# STM32_microcontroller_RF.net
KiCad netlist of a schematic drawn in Altium Designer
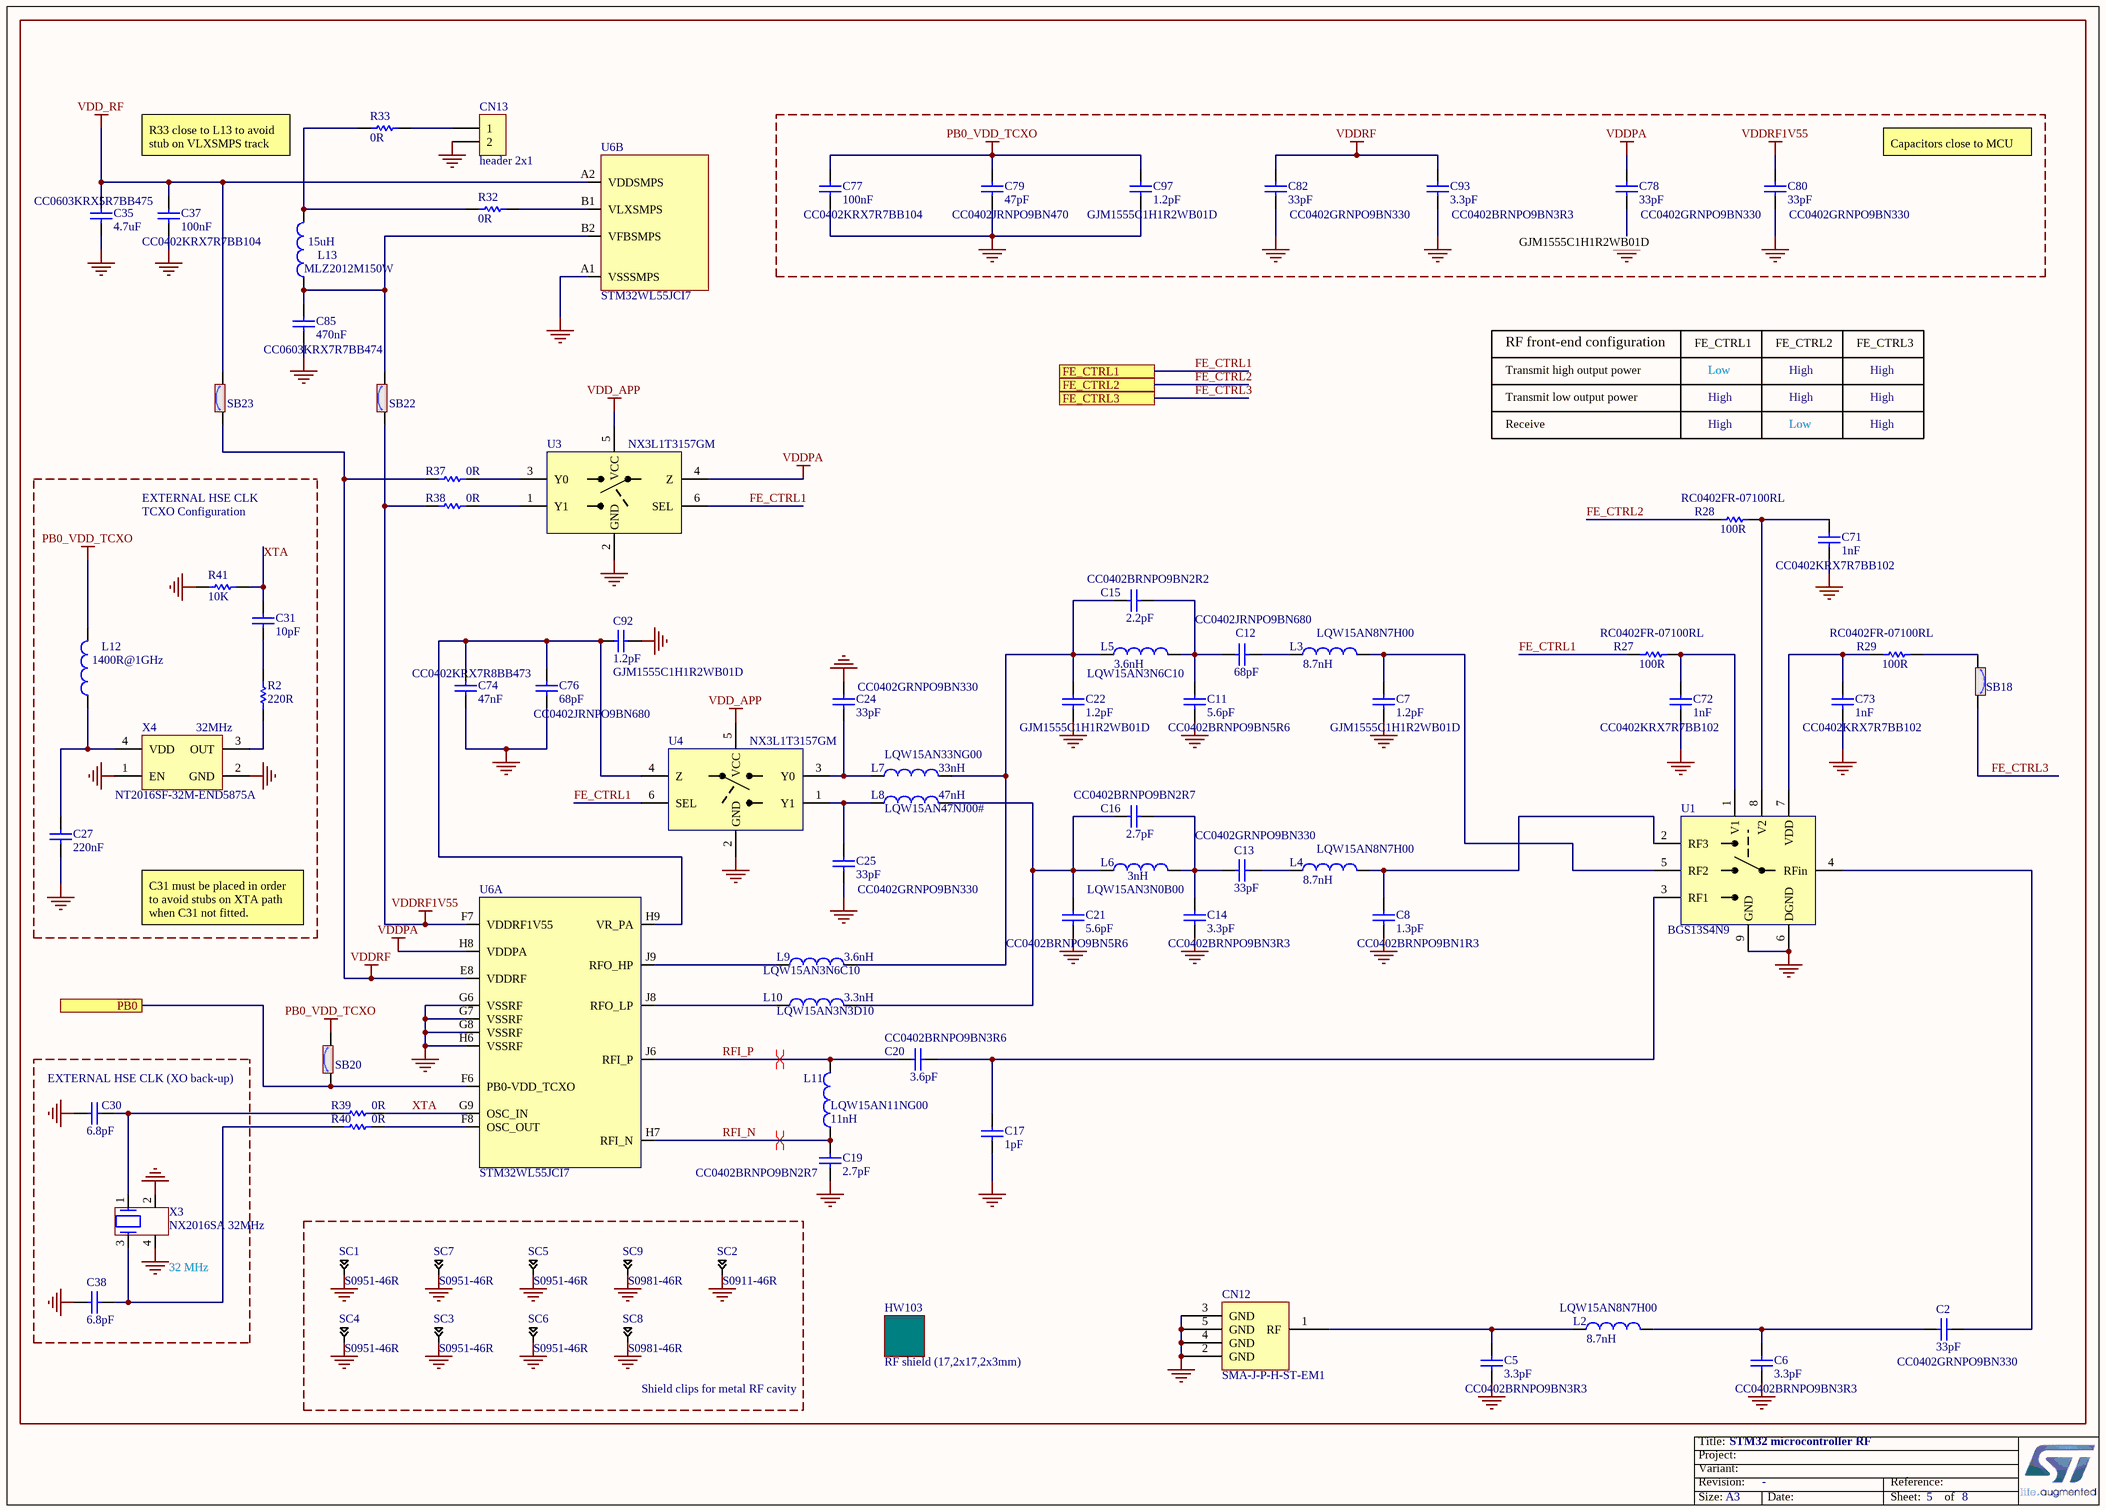
[diagram p0: STM32_microcontroller_RF.SchDoc]

(export (version "E")
  (design (tool "Eeschema 10.0.6"))
  (components
    (comp (ref "C2")
      (value "33pF")
      (footprint "C0402")
      (description "Capacitor, MLCC, 33pF, 50V, NPO, +/-2%, 0402, T=0,5mm")
      (fields
        (field (name "INTERNAL_PART_NUMBER") "MCD-01784")
        (field (name "MANUFACTURER_PART_NUMBER") "CC0402GRNPO9BN330")
        (field (name "MANUFACTURER") "YAGEO")
        (field (name "PROVIDED_BY") "SUBCO")
      )
      (libsource (lib "MCD_PARTS_database") (part "Capacitor"))
    )
    (comp (ref "C5")
      (value "3.3pF")
      (footprint "C0402")
      (description "Capacitor, MLCC, 3.3pF, 50V, NPO, +/-0.1pF, 0402, T=0,5mm")
      (fields
        (field (name "INTERNAL_PART_NUMBER") "MCD-01775")
        (field (name "MANUFACTURER_PART_NUMBER") "CC0402BRNPO9BN3R3")
        (field (name "MANUFACTURER") "YAGEO")
        (field (name "PROVIDED_BY") "SUBCO")
      )
      (libsource (lib "MCD_PARTS_database") (part "Capacitor"))
    )
    (comp (ref "C6")
      (value "3.3pF")
      (footprint "C0402")
      (description "Capacitor, MLCC, 3.3pF, 50V, NPO, +/-0.1pF, 0402, T=0,5mm")
      (fields
        (field (name "INTERNAL_PART_NUMBER") "MCD-01775")
        (field (name "MANUFACTURER_PART_NUMBER") "CC0402BRNPO9BN3R3")
        (field (name "MANUFACTURER") "YAGEO")
        (field (name "PROVIDED_BY") "SUBCO")
      )
      (libsource (lib "MCD_PARTS_database") (part "Capacitor"))
    )
    (comp (ref "C7")
      (value "1.2pF")
      (footprint "C0402")
      (description "Capacitor, High Q type for high frequency and high power, SMD, 1.2pF, 50V, 0,05pf, 0402")
      (fields
        (field (name "INTERNAL_PART_NUMBER") "MCD-02065")
        (field (name "MANUFACTURER") "MURATA")
        (field (name "MANUFACTURER_PART_NUMBER") "GJM1555C1H1R2WB01D")
      )
      (libsource (lib "MCD_PARTS_database") (part "Capacitor"))
    )
    (comp (ref "C8")
      (value "1.3pF")
      (footprint "C0402")
      (description "Capacitor, MLCC, 1.3pF, 50V, NPO, +/-0.1pF, 0402, T=0,5mm")
      (fields
        (field (name "INTERNAL_PART_NUMBER") "MCD-01772")
        (field (name "MANUFACTURER_PART_NUMBER") "CC0402BRNPO9BN1R3")
        (field (name "MANUFACTURER") "YAGEO")
        (field (name "PROVIDED_BY") "SUBCO")
      )
      (libsource (lib "MCD_PARTS_database") (part "Capacitor"))
    )
    (comp (ref "C11")
      (value "5.6pF")
      (footprint "C0402")
      (description "Capacitor, MLCC, 5.6pF, 50V, NPO, +/- 0.1pF, 0402, T=0,5mm")
      (fields
        (field (name "INTERNAL_PART_NUMBER") "MCD-01374")
        (field (name "MANUFACTURER") "YAGEO")
        (field (name "MANUFACTURER_PART_NUMBER") "CC0402BRNPO9BN5R6")
      )
      (libsource (lib "MCD_PARTS_database") (part "Capacitor"))
    )
    (comp (ref "C12")
      (value "68pF")
      (footprint "C0402")
      (description "Capacitor, MLCC, 68pF, 50V, NPO, +/-5%, 0402, T=0,5mm")
      (fields
        (field (name "INTERNAL_PART_NUMBER") "MCD-01604")
        (field (name "MANUFACTURER") "YAGEO")
        (field (name "MANUFACTURER_PART_NUMBER") "CC0402JRNPO9BN680")
      )
      (libsource (lib "MCD_PARTS_database") (part "Capacitor"))
    )
    (comp (ref "C13")
      (value "33pF")
      (footprint "C0402")
      (description "Capacitor, MLCC, 33pF, 50V, NPO, +/-2%, 0402, T=0,5mm")
      (fields
        (field (name "INTERNAL_PART_NUMBER") "MCD-01784")
        (field (name "MANUFACTURER_PART_NUMBER") "CC0402GRNPO9BN330")
        (field (name "MANUFACTURER") "YAGEO")
        (field (name "PROVIDED_BY") "SUBCO")
      )
      (libsource (lib "MCD_PARTS_database") (part "Capacitor"))
    )
    (comp (ref "C14")
      (value "3.3pF")
      (footprint "C0402")
      (description "Capacitor, MLCC, 3.3pF, 50V, NPO, +/-0.1pF, 0402, T=0,5mm")
      (fields
        (field (name "INTERNAL_PART_NUMBER") "MCD-01775")
        (field (name "MANUFACTURER_PART_NUMBER") "CC0402BRNPO9BN3R3")
        (field (name "MANUFACTURER") "YAGEO")
        (field (name "PROVIDED_BY") "SUBCO")
      )
      (libsource (lib "MCD_PARTS_database") (part "Capacitor"))
    )
    (comp (ref "C15")
      (value "2.2pF")
      (footprint "C0402")
      (description "Capacitor, MLCC, 2.2pF, 50V, NPO, +/-0.1pF, 0402, T=0,5mm")
      (fields
        (field (name "INTERNAL_PART_NUMBER") "MCD-01773")
        (field (name "MANUFACTURER") "YAGEO")
        (field (name "MANUFACTURER_PART_NUMBER") "CC0402BRNPO9BN2R2")
      )
      (libsource (lib "MCD_PARTS_database") (part "Capacitor"))
    )
    (comp (ref "C16")
      (value "2.7pF")
      (footprint "C0402")
      (description "Capacitor, MLCC, 2.7pF, 50V, NPO, +/-0.1pF, 0402, T=0,5mm")
      (fields
        (field (name "INTERNAL_PART_NUMBER") "MCD-01774")
        (field (name "MANUFACTURER_PART_NUMBER") "CC0402BRNPO9BN2R7")
        (field (name "MANUFACTURER") "YAGEO")
        (field (name "PROVIDED_BY") "SUBCO")
      )
      (libsource (lib "MCD_PARTS_database") (part "Capacitor"))
    )
    (comp (ref "C17")
      (value "1pF")
      (footprint "C0402")
      (description "Capacitor, MLCC, 1pF, 50V, NPO, +/-0.1pF, 0402, T=0,5mm")
      (fields (field (name "INTERNAL_PART_NUMBER") "MCD-01600") (field (name "MANUFACTURER") "YAGEO"))
      (libsource (lib "MCD_PARTS_database") (part "Capacitor"))
    )
    (comp (ref "C19")
      (value "2.7pF")
      (footprint "C0402")
      (description "Capacitor, MLCC, 2.7pF, 50V, NPO, +/-0.1pF, 0402, T=0,5mm")
      (fields
        (field (name "INTERNAL_PART_NUMBER") "MCD-01774")
        (field (name "MANUFACTURER_PART_NUMBER") "CC0402BRNPO9BN2R7")
        (field (name "MANUFACTURER") "YAGEO")
        (field (name "PROVIDED_BY") "SUBCO")
      )
      (libsource (lib "MCD_PARTS_database") (part "Capacitor"))
    )
    (comp (ref "C20")
      (value "3.6pF")
      (footprint "C0402")
      (description "Capacitor, MLCC, 3.6pF, 50V, NPO, +/-0.1pF, 0402, T=0,5mm")
      (fields
        (field (name "INTERNAL_PART_NUMBER") "MCD-01776")
        (field (name "MANUFACTURER_PART_NUMBER") "CC0402BRNPO9BN3R6")
        (field (name "MANUFACTURER") "YAGEO")
        (field (name "PROVIDED_BY") "SUBCO")
      )
      (libsource (lib "MCD_PARTS_database") (part "Capacitor"))
    )
    (comp (ref "C21")
      (value "5.6pF")
      (footprint "C0402")
      (description "Capacitor, MLCC, 5.6pF, 50V, NPO, +/- 0.1pF, 0402, T=0,5mm")
      (fields
        (field (name "INTERNAL_PART_NUMBER") "MCD-01374")
        (field (name "MANUFACTURER_PART_NUMBER") "CC0402BRNPO9BN5R6")
        (field (name "MANUFACTURER") "YAGEO")
        (field (name "PROVIDED_BY") "SUBCO")
      )
      (libsource (lib "MCD_PARTS_database") (part "Capacitor"))
    )
    (comp (ref "C22")
      (value "1.2pF")
      (footprint "C0402")
      (description "Capacitor, High Q type for high frequency and high power, SMD, 1.2pF, 50V, 0,05pf, 0402")
      (fields
        (field (name "INTERNAL_PART_NUMBER") "MCD-02065")
        (field (name "MANUFACTURER") "MURATA")
        (field (name "MANUFACTURER_PART_NUMBER") "GJM1555C1H1R2WB01D")
      )
      (libsource (lib "MCD_PARTS_database") (part "Capacitor"))
    )
    (comp (ref "C24")
      (value "33pF")
      (footprint "C0402")
      (description "Capacitor, MLCC, 33pF, 50V, NPO, +/-2%, 0402, T=0,5mm")
      (fields
        (field (name "INTERNAL_PART_NUMBER") "MCD-01784")
        (field (name "MANUFACTURER_PART_NUMBER") "CC0402GRNPO9BN330")
        (field (name "MANUFACTURER") "YAGEO")
        (field (name "PROVIDED_BY") "SUBCO")
      )
      (libsource (lib "MCD_PARTS_database") (part "Capacitor"))
    )
    (comp (ref "C25")
      (value "33pF")
      (footprint "C0402")
      (description "Capacitor, MLCC, 33pF, 50V, NPO, +/-2%, 0402, T=0,5mm")
      (fields
        (field (name "INTERNAL_PART_NUMBER") "MCD-01784")
        (field (name "MANUFACTURER_PART_NUMBER") "CC0402GRNPO9BN330")
        (field (name "MANUFACTURER") "YAGEO")
        (field (name "PROVIDED_BY") "SUBCO")
      )
      (libsource (lib "MCD_PARTS_database") (part "Capacitor"))
    )
    (comp (ref "C27")
      (value "220nF")
      (footprint "C0402")
      (description "Capacitor, MLCC, 220nF, 16V, X7R, +/-10%, ,0402, T=0,5mm")
      (fields (field (name "INTERNAL_PART_NUMBER") "MCD-00602") (field (name "MANUFACTURER") "TDK"))
      (libsource (lib "MCD_PARTS_database") (part "Capacitor"))
    )
    (comp (ref "C30")
      (value "6.8pF")
      (footprint "C0402")
      (description "Capacitor, MLCC, 6.8pF, 50V, NPO, +-0.25pF, 0402, T=0.5mm")
      (fields
        (field (name "INTERNAL_PART_NUMBER") "MCD-00674")
        (field (name "MANUFACTURER_PART_NUMBER") "CC0402CRNPO9BN6R8")
        (field (name "PROVIDED_BY") "SUBCO")
      )
      (libsource (lib "MCD_PARTS_database") (part "Capacitor"))
    )
    (comp (ref "C31")
      (value "10pF")
      (footprint "C0402")
      (description "Capacitor, MLCC, 10pF, 50V, NPO, +/-5%, 0402, T=0,5mm")
      (fields (field (name "INTERNAL_PART_NUMBER") "MCD-00015") (field (name "MANUFACTURER") "YAGEO"))
      (libsource (lib "MCD_PARTS_database") (part "Capacitor"))
    )
    (comp (ref "C35")
      (value "4.7uF")
      (footprint "C0603")
      (description "Capacitor, MLCC, 4.7uF, 16V, X5R, 10%, 0603, T=0.8mm")
      (fields
        (field (name "INTERNAL_PART_NUMBER") "MCD-00009")
        (field (name "MANUFACTURER_PART_NUMBER") "CC0603KRX5R7BB475")
        (field (name "MANUFACTURER") "YAGEO")
        (field (name "PROVIDED_BY") "SUBCO")
      )
      (libsource (lib "MCD_PARTS_database") (part "Capacitor"))
    )
    (comp (ref "C37")
      (value "100nF")
      (footprint "C0402")
      (description "Capacitor, MLCC, 100nF, 16V, X7R, 10%, 0402, T=0,5mm")
      (fields
        (field (name "INTERNAL_PART_NUMBER") "MCD-00102")
        (field (name "MANUFACTURER_PART_NUMBER") "CC0402KRX7R7BB104")
        (field (name "MANUFACTURER") "YAGEO")
        (field (name "PROVIDED_BY") "SUBCO")
      )
      (libsource (lib "MCD_PARTS_database") (part "Capacitor"))
    )
    (comp (ref "C38")
      (value "6.8pF")
      (footprint "C0402")
      (description "Capacitor, MLCC, 6.8pF, 50V, NPO, +-0.25pF, 0402, T=0.5mm")
      (fields
        (field (name "INTERNAL_PART_NUMBER") "MCD-00674")
        (field (name "MANUFACTURER_PART_NUMBER") "CC0402CRNPO9BN6R8")
        (field (name "PROVIDED_BY") "SUBCO")
      )
      (libsource (lib "MCD_PARTS_database") (part "Capacitor"))
    )
    (comp (ref "C71")
      (value "1nF")
      (footprint "C0402")
      (description "Capacitor, MLCC, 1nF, 16V, X7R, 10%, 0402, T=0.5mm")
      (fields
        (field (name "INTERNAL_PART_NUMBER") "MCD-00198")
        (field (name "MANUFACTURER_PART_NUMBER") "CC0402KRX7R7BB102")
        (field (name "MANUFACTURER") "YAGEO")
        (field (name "PROVIDED_BY") "SUBCO")
      )
      (libsource (lib "MCD_PARTS_database") (part "Capacitor"))
    )
    (comp (ref "C72")
      (value "1nF")
      (footprint "C0402")
      (description "Capacitor, MLCC, 1nF, 16V, X7R, 10%, 0402, T=0.5mm")
      (fields
        (field (name "INTERNAL_PART_NUMBER") "MCD-00198")
        (field (name "MANUFACTURER_PART_NUMBER") "CC0402KRX7R7BB102")
        (field (name "MANUFACTURER") "YAGEO")
        (field (name "PROVIDED_BY") "SUBCO")
      )
      (libsource (lib "MCD_PARTS_database") (part "Capacitor"))
    )
    (comp (ref "C73")
      (value "1nF")
      (footprint "C0402")
      (description "Capacitor, MLCC, 1nF, 16V, X7R, 10%, 0402, T=0.5mm")
      (fields
        (field (name "INTERNAL_PART_NUMBER") "MCD-00198")
        (field (name "MANUFACTURER_PART_NUMBER") "CC0402KRX7R7BB102")
        (field (name "MANUFACTURER") "YAGEO")
        (field (name "PROVIDED_BY") "SUBCO")
      )
      (libsource (lib "MCD_PARTS_database") (part "Capacitor"))
    )
    (comp (ref "C74")
      (value "47nF")
      (footprint "C0402")
      (description "Capacitor, MLCC, 47nF, 25V, X7R, +-10%, 0402, T=0,5mm")
      (fields
        (field (name "INTERNAL_PART_NUMBER") "MCD-01605")
        (field (name "MANUFACTURER_PART_NUMBER") "CC0402KRX7R8BB473")
        (field (name "MANUFACTURER") "YAGEO")
        (field (name "PROVIDED_BY") "SUBCO")
      )
      (libsource (lib "MCD_PARTS_database") (part "Capacitor"))
    )
    (comp (ref "C76")
      (value "68pF")
      (footprint "C0402")
      (description "Capacitor, MLCC, 68pF, 50V, NPO, +-5%, 0402, T=0,5mm")
      (fields
        (field (name "INTERNAL_PART_NUMBER") "MCD-01604")
        (field (name "MANUFACTURER_PART_NUMBER") "CC0402JRNPO9BN680")
        (field (name "MANUFACTURER") "YAGEO")
        (field (name "PROVIDED_BY") "SUBCO")
      )
      (libsource (lib "MCD_PARTS_database") (part "Capacitor"))
    )
    (comp (ref "C77")
      (value "100nF")
      (footprint "C0402")
      (description "Capacitor, MLCC, 100nF, 16V, X7R, 10%, 0402, T=0,5mm")
      (fields
        (field (name "INTERNAL_PART_NUMBER") "MCD-00102")
        (field (name "MANUFACTURER_PART_NUMBER") "CC0402KRX7R7BB104")
        (field (name "MANUFACTURER") "YAGEO")
        (field (name "PROVIDED_BY") "SUBCO")
      )
      (libsource (lib "MCD_PARTS_database") (part "Capacitor"))
    )
    (comp (ref "C78")
      (value "33pF")
      (footprint "C0402")
      (description "Capacitor, MLCC, 33pF, 50V, NPO, +/-2%, 0402, T=0,5mm")
      (fields
        (field (name "INTERNAL_PART_NUMBER") "MCD-01784")
        (field (name "MANUFACTURER_PART_NUMBER") "CC0402GRNPO9BN330")
        (field (name "MANUFACTURER") "YAGEO")
        (field (name "PROVIDED_BY") "SUBCO")
      )
      (libsource (lib "MCD_PARTS_database") (part "Capacitor"))
    )
    (comp (ref "C79")
      (value "47pF")
      (footprint "C0402")
      (description "Capacitor, MLCC, 147pF, 50V, NPO, +-5%, 0402, T=0,5mm")
      (fields
        (field (name "INTERNAL_PART_NUMBER") "MCD-01603")
        (field (name "MANUFACTURER_PART_NUMBER") "CC0402JRNPO9BN470")
        (field (name "MANUFACTURER") "YAGEO")
        (field (name "PROVIDED_BY") "SUBCO")
      )
      (libsource (lib "MCD_PARTS_database") (part "Capacitor"))
    )
    (comp (ref "C80")
      (value "33pF")
      (footprint "C0402")
      (description "Capacitor, MLCC, 33pF, 50V, NPO, +/-2%, 0402, T=0,5mm")
      (fields
        (field (name "INTERNAL_PART_NUMBER") "MCD-01784")
        (field (name "MANUFACTURER_PART_NUMBER") "CC0402GRNPO9BN330")
        (field (name "MANUFACTURER") "YAGEO")
        (field (name "PROVIDED_BY") "SUBCO")
      )
      (libsource (lib "MCD_PARTS_database") (part "Capacitor"))
    )
    (comp (ref "C82")
      (value "33pF")
      (footprint "C0402")
      (description "Capacitor, MLCC, 33pF, 50V, NPO, +/-2%, 0402, T=0,5mm")
      (fields
        (field (name "INTERNAL_PART_NUMBER") "MCD-01784")
        (field (name "MANUFACTURER_PART_NUMBER") "CC0402GRNPO9BN330")
        (field (name "MANUFACTURER") "YAGEO")
        (field (name "PROVIDED_BY") "SUBCO")
      )
      (libsource (lib "MCD_PARTS_database") (part "Capacitor"))
    )
    (comp (ref "C85")
      (value "470nF")
      (footprint "C0603")
      (description "Capacitor, MLCC, 470nF, 16V, X7R, 10%, 0603, T=0.8mm")
      (fields
        (field (name "INTERNAL_PART_NUMBER") "MCD-01006")
        (field (name "MANUFACTURER_PART_NUMBER") "CC0603KRX7R7BB474")
        (field (name "MANUFACTURER") "YAGEO")
        (field (name "PROVIDED_BY") "SUBCO")
      )
      (libsource (lib "MCD_PARTS_database") (part "Capacitor"))
    )
    (comp (ref "C92")
      (value "1.2pF")
      (footprint "C0402")
      (description "Capacitor, High Q type for high frequency and high power, SMD, 1.2pF, 50V, 0,05pf, 0402")
      (fields
        (field (name "INTERNAL_PART_NUMBER") "MCD-02065")
        (field (name "MANUFACTURER") "MURATA")
        (field (name "MANUFACTURER_PART_NUMBER") "GJM1555C1H1R2WB01D")
      )
      (libsource (lib "MCD_PARTS_database") (part "Capacitor"))
    )
    (comp (ref "C93")
      (value "3.3pF")
      (footprint "C0402")
      (description "Capacitor, MLCC, 3.3pF, 50V, NPO, +/-0.1pF, 0402, T=0,5mm")
      (fields
        (field (name "INTERNAL_PART_NUMBER") "MCD-01775")
        (field (name "MANUFACTURER") "YAGEO")
        (field (name "MANUFACTURER_PART_NUMBER") "CC0402BRNPO9BN3R3")
      )
      (libsource (lib "MCD_PARTS_database") (part "Capacitor"))
    )
    (comp (ref "C97")
      (value "1.2pF")
      (footprint "C0402")
      (description "Capacitor, High Q type for high frequency and high power, SMD, 1.2pF, 50V, 0,05pf, 0402")
      (fields
        (field (name "INTERNAL_PART_NUMBER") "MCD-02065")
        (field (name "MANUFACTURER") "MURATA")
        (field (name "MANUFACTURER_PART_NUMBER") "GJM1555C1H1R2WB01D")
      )
      (libsource (lib "MCD_PARTS_database") (part "Capacitor"))
    )
    (comp (ref "CN12")
      (value "SMA-J-P-H-ST-EM1")
      (footprint "CON_SAMTEC_SMA-J-P-X-ST-EM1")
      (description "RF SMA connector PCB edge")
      (fields
        (field (name "INTERNAL_PART_NUMBER") "MCD-00279")
        (field (name "MANUFACTURER") "SAMTEC")
        (field (name "PROVIDED_BY") "SUBCO")
      )
      (libsource (lib "MCD_PARTS_database") (part "SMA-J-P-H-ST-EM1"))
    )
    (comp (ref "CN13")
      (value "header 2x1")
      (footprint "CON_988-JIUBABA_PHFS25-11-02-G0B115-T-1")
      (description "Header, 2x1, 2.54mm, VR, TH, Height 6mm/3mm")
      (fields
        (field (name "INTERNAL_PART_NUMBER") "MCD-00314")
        (field (name "MANUFACTURER_PART_NUMBER") "PHFS25-11-02-G0B115-T-1")
        (field (name "PROVIDED_BY") "SUBCO")
      )
      (libsource (lib "MCD_PARTS_database") (part "Header 2x1"))
    )
    (comp (ref "HW103")
      (value "RF shield (17,2x17,2x3mm)")
      (footprint "SHIELD_RF_ST-CUSTOM_17P2X17P2_H3")
      (description "RF shield (17,2x17,2x3mm), Brass with Sn finishing, Sheet tickness : 0,2mm")
      (fields (field (name "INTERNAL_PART_NUMBER") "MCD-02088") (field (name "BMS_PART_NUMBER") "TBD"))
      (libsource (lib "MCD_PARTS_database") (part "Daughter_Board"))
    )
    (comp (ref "L2")
      (value "8.7nH")
      (footprint "IND_0402_MURATA_LQW15AN_H0P5")
      (description "0402 inductor, 8.7nH +/-3%, 540mA max, 0.14 ohm DC max, Q min = 25")
      (fields
        (field (name "INTERNAL_PART_NUMBER") "MCD-01768")
        (field (name "MANUFACTURER_PART_NUMBER") "LQW15AN8N7H00")
        (field (name "MANUFACTURER") "MURATA")
        (field (name "PROVIDED_BY") "SUBCO")
      )
      (libsource (lib "MCD_PARTS_database") (part "Inductor"))
    )
    (comp (ref "L3")
      (value "8.7nH")
      (footprint "IND_0402_MURATA_LQW15AN_H0P5")
      (description "0402 inductor, 8.7nH +/-3%, 540mA max, 0.14 ohm DC max, Q min = 25")
      (fields
        (field (name "INTERNAL_PART_NUMBER") "MCD-01768")
        (field (name "MANUFACTURER") "MURATA")
        (field (name "MANUFACTURER_PART_NUMBER") "LQW15AN8N7H00")
      )
      (libsource (lib "MCD_PARTS_database") (part "Inductor"))
    )
    (comp (ref "L4")
      (value "8.7nH")
      (footprint "IND_0402_MURATA_LQW15AN_H0P5")
      (description "0402 inductor, 8.7nH +/-3%, 540mA max, 0.14 ohm DC max, Q min = 25")
      (fields
        (field (name "INTERNAL_PART_NUMBER") "MCD-01768")
        (field (name "MANUFACTURER_PART_NUMBER") "LQW15AN8N7H00")
        (field (name "MANUFACTURER") "MURATA")
        (field (name "PROVIDED_BY") "SUBCO")
      )
      (libsource (lib "MCD_PARTS_database") (part "Inductor"))
    )
    (comp (ref "L5")
      (value "3.6nH")
      (footprint "IND_0402_MURATA_LQW15AN_H0P5")
      (description "0402 inductor, 3.6nH +/-0.2nH, 900mA max, 0.04 ohm DC max, Q min = 30")
      (fields
        (field (name "INTERNAL_PART_NUMBER") "MCD-01762")
        (field (name "MANUFACTURER") "MURATA")
        (field (name "MANUFACTURER_PART_NUMBER") "LQW15AN3N6C10")
      )
      (libsource (lib "MCD_PARTS_database") (part "Inductor"))
    )
    (comp (ref "L6")
      (value "3nH")
      (footprint "IND_0402_MURATA_LQW15AN_H0P5")
      (description "0402 inductor, 3nH +-0.1nH, 750mA max, 0.07 ohm DC max, Q min = 20")
      (fields
        (field (name "INTERNAL_PART_NUMBER") "MCD-01922")
        (field (name "MANUFACTURER_PART_NUMBER") "LQW15AN3N0B00")
        (field (name "MANUFACTURER") "MURATA")
        (field (name "PROVIDED_BY") "SUBCO")
      )
      (libsource (lib "MCD_PARTS_database") (part "Inductor"))
    )
    (comp (ref "L7")
      (value "33nH")
      (footprint "IND_0402_MURATA_LQW15AN_H0P5")
      (description "Inductor, 33nH +/-2%, 260mA max , 0.63 ohm DC max, 0402, Q min = 25.")
      (fields
        (field (name "INTERNAL_PART_NUMBER") "MCD-02069")
        (field (name "MANUFACTURER") "MURATA")
        (field (name "MANUFACTURER_PART_NUMBER") "LQW15AN33NG00")
      )
      (libsource (lib "MCD_PARTS_database") (part "Inductor"))
    )
    (comp (ref "L8")
      (value "47nH")
      (footprint "IND_0402_MURATA_LQW15AN2N4C00X")
      (description "Inductor, 47nH, +-5%, 210mA, 1.08ohm DC max, 0402")
      (fields
        (field (name "INTERNAL_PART_NUMBER") "MCD-01609")
        (field (name "MANUFACTURER_PART_NUMBER") "LQW15AN47NJ00#")
        (field (name "MANUFACTURER") "MURATA")
        (field (name "PROVIDED_BY") "SUBCO")
      )
      (libsource (lib "MCD_PARTS_database") (part "Inductor"))
    )
    (comp (ref "L9")
      (value "3.6nH")
      (footprint "IND_0402_MURATA_LQW15AN_H0P5")
      (description "0402 inductor, 3.6nH +/-0.2nH, 900mA max, 0.04 ohm DC max, Q min = 30")
      (fields
        (field (name "INTERNAL_PART_NUMBER") "MCD-01762")
        (field (name "MANUFACTURER_PART_NUMBER") "LQW15AN3N6C10")
        (field (name "MANUFACTURER") "MURATA")
        (field (name "PROVIDED_BY") "SUBCO")
      )
      (libsource (lib "MCD_PARTS_database") (part "Inductor"))
    )
    (comp (ref "L10")
      (value "3.3nH")
      (footprint "IND_0402_MURATA_LQW15AN_H0P5")
      (description "0402 inductor, 3.3nH +-0.5nH, 900mA max, 0.04 ohm DC max, Q min = 30")
      (fields
        (field (name "INTERNAL_PART_NUMBER") "MCD-01761")
        (field (name "MANUFACTURER_PART_NUMBER") "LQW15AN3N3D10")
        (field (name "MANUFACTURER") "MURATA")
        (field (name "PROVIDED_BY") "SUBCO")
      )
      (libsource (lib "MCD_PARTS_database") (part "Inductor"))
    )
    (comp (ref "L11")
      (value "11nH")
      (footprint "IND_0402_MURATA_LQW15AN_H0P5")
      (description "0402 inductor, 11nH +-2%, 500mA max, 0.14 ohm DC max, Q min = 30")
      (fields
        (field (name "INTERNAL_PART_NUMBER") "MCD-01921")
        (field (name "MANUFACTURER_PART_NUMBER") "LQW15AN11NG00")
        (field (name "MANUFACTURER") "MURATA")
        (field (name "PROVIDED_BY") "SUBCO")
      )
      (libsource (lib "MCD_PARTS_database") (part "Inductor"))
    )
    (comp (ref "L12")
      (value "1400R@1GHz")
      (footprint "IND_0402_MURATA_BLM15H_H0P5")
      (description "ferrite bead, 1400ohms at 1GHz, 250mA, 1.1ohms DC max")
      (fields
        (field (name "INTERNAL_PART_NUMBER") "MCD-01610")
        (field (name "MANUFACTURER_PART_NUMBER") "BLM15HG102SN1#")
        (field (name "PROVIDED_BY") "SUBCO")
      )
      (libsource (lib "MCD_PARTS_database") (part "Inductor"))
    )
    (comp (ref "L13")
      (value "15uH")
      (footprint "IND_TDK_MLZ2012M150W")
      (description "MLZ2012 Multilayer Shielded Inductor 15uH, +/-5%")
      (fields
        (field (name "INTERNAL_PART_NUMBER") "MCD-01433")
        (field (name "MANUFACTURER_PART_NUMBER") "MLZ2012M150W")
        (field (name "MANUFACTURER") "TDK")
        (field (name "PROVIDED_BY") "SUBCO")
      )
      (libsource (lib "MCD_PARTS_database") (part "Inductor"))
    )
    (comp (ref "R2")
      (value "220R")
      (footprint "R0402")
      (description "Resistor,220R,0402,1%,1/16W")
      (fields
        (field (name "INTERNAL_PART_NUMBER") "MCD-00427")
        (field (name "MANUFACTURER_PART_NUMBER") "RC0402FR-07220RL")
        (field (name "PROVIDED_BY") "SUBCO")
      )
      (libsource (lib "MCD_PARTS_database") (part "Resistor"))
    )
    (comp (ref "R27")
      (value "100R")
      (footprint "R0402")
      (description "Resistor,100R,0402,1%,1/16W")
      (fields
        (field (name "INTERNAL_PART_NUMBER") "MCD-00119")
        (field (name "MANUFACTURER_PART_NUMBER") "RC0402FR-07100RL")
        (field (name "MANUFACTURER") "YAGEO")
        (field (name "PROVIDED_BY") "SUBCO")
      )
      (libsource (lib "MCD_PARTS_database") (part "Resistor"))
    )
    (comp (ref "R28")
      (value "100R")
      (footprint "R0402")
      (description "Resistor,100R,0402,1%,1/16W")
      (fields
        (field (name "INTERNAL_PART_NUMBER") "MCD-00119")
        (field (name "MANUFACTURER_PART_NUMBER") "RC0402FR-07100RL")
        (field (name "MANUFACTURER") "YAGEO")
        (field (name "PROVIDED_BY") "SUBCO")
      )
      (libsource (lib "MCD_PARTS_database") (part "Resistor"))
    )
    (comp (ref "R29")
      (value "100R")
      (footprint "R0402")
      (description "Resistor,100R,0402,1%,1/16W")
      (fields
        (field (name "INTERNAL_PART_NUMBER") "MCD-00119")
        (field (name "MANUFACTURER_PART_NUMBER") "RC0402FR-07100RL")
        (field (name "MANUFACTURER") "YAGEO")
        (field (name "PROVIDED_BY") "SUBCO")
      )
      (libsource (lib "MCD_PARTS_database") (part "Resistor"))
    )
    (comp (ref "R32")
      (value "0R")
      (footprint "R0402")
      (description "Resistor,0R,0402,5%,1/16W")
      (fields
        (field (name "INTERNAL_PART_NUMBER") "MCD-00052")
        (field (name "MANUFACTURER_PART_NUMBER") "RC0402JR-070RL")
        (field (name "PROVIDED_BY") "SUBCO")
      )
      (libsource (lib "MCD_PARTS_database") (part "Resistor"))
    )
    (comp (ref "R33")
      (value "0R")
      (footprint "R0402")
      (description "Resistor,0R,0402,5%,1/16W")
      (fields
        (field (name "INTERNAL_PART_NUMBER") "MCD-00052")
        (field (name "MANUFACTURER_PART_NUMBER") "RC0402JR-070RL")
        (field (name "PROVIDED_BY") "SUBCO")
      )
      (libsource (lib "MCD_PARTS_database") (part "Resistor"))
    )
    (comp (ref "R37")
      (value "0R")
      (footprint "R0402")
      (description "Resistor,0R,0402,5%,1/16W")
      (fields
        (field (name "INTERNAL_PART_NUMBER") "MCD-00052")
        (field (name "MANUFACTURER_PART_NUMBER") "RC0402JR-070RL")
        (field (name "PROVIDED_BY") "SUBCO")
      )
      (libsource (lib "MCD_PARTS_database") (part "Resistor"))
    )
    (comp (ref "R38")
      (value "0R")
      (footprint "R0402")
      (description "Resistor,0R,0402,5%,1/16W")
      (fields
        (field (name "INTERNAL_PART_NUMBER") "MCD-00052")
        (field (name "MANUFACTURER_PART_NUMBER") "RC0402JR-070RL")
        (field (name "PROVIDED_BY") "SUBCO")
      )
      (libsource (lib "MCD_PARTS_database") (part "Resistor"))
    )
    (comp (ref "R39")
      (value "0R")
      (footprint "R0402")
      (description "Resistor,0R,0402,5%,1/16W")
      (fields
        (field (name "INTERNAL_PART_NUMBER") "MCD-00052")
        (field (name "MANUFACTURER_PART_NUMBER") "RC0402JR-070RL")
        (field (name "PROVIDED_BY") "SUBCO")
      )
      (libsource (lib "MCD_PARTS_database") (part "Resistor"))
    )
    (comp (ref "R40")
      (value "0R")
      (footprint "R0402")
      (description "Resistor,0R,0402,5%,1/16W")
      (fields
        (field (name "INTERNAL_PART_NUMBER") "MCD-00052")
        (field (name "MANUFACTURER_PART_NUMBER") "RC0402JR-070RL")
        (field (name "PROVIDED_BY") "SUBCO")
      )
      (libsource (lib "MCD_PARTS_database") (part "Resistor"))
    )
    (comp (ref "R41")
      (value "10K")
      (footprint "R0402")
      (description "Resistor,10K,0402,1%,1/16W")
      (fields
        (field (name "INTERNAL_PART_NUMBER") "MCD-00053")
        (field (name "MANUFACTURER_PART_NUMBER") "RC0402FR-0710KL")
        (field (name "PROVIDED_BY") "SUBCO")
      )
      (libsource (lib "MCD_PARTS_database") (part "Resistor"))
    )
    (comp (ref "SB18")
      (value "~")
      (footprint "SOLDER-BRIDGE_R0603-0R")
      (description "Solder Bridge ON")
      (fields
        (field (name "INTERNAL_PART_NUMBER") "MCD-00071")
        (field (name "MANUFACTURER_PART_NUMBER") "RC0603JR-070RL")
        (field (name "PROVIDED_BY") "SUBCO")
      )
      (libsource (lib "") (part "SB_ON_1"))
    )
    (comp (ref "SB20")
      (value "~")
      (footprint "SOLDER-BRIDGE_R0603-0R")
      (description "Solder Bridge ON")
      (fields
        (field (name "INTERNAL_PART_NUMBER") "MCD-00071")
        (field (name "MANUFACTURER_PART_NUMBER") "RC0603JR-070RL")
        (field (name "PROVIDED_BY") "SUBCO")
      )
      (libsource (lib "MCD_PARTS_database") (part "SB_ON"))
    )
    (comp (ref "SB22")
      (value "~")
      (footprint "SOLDER-BRIDGE_R0603-0R")
      (description "Solder Bridge ON")
      (fields
        (field (name "INTERNAL_PART_NUMBER") "MCD-00071")
        (field (name "MANUFACTURER_PART_NUMBER") "RC0603JR-070RL")
        (field (name "PROVIDED_BY") "SUBCO")
      )
      (libsource (lib "MCD_PARTS_database") (part "SB_ON"))
    )
    (comp (ref "SB23")
      (value "~")
      (footprint "SOLDER-BRIDGE_R0603-0R")
      (description "Solder Bridge ON")
      (fields
        (field (name "INTERNAL_PART_NUMBER") "MCD-00071")
        (field (name "MANUFACTURER_PART_NUMBER") "RC0603JR-070RL")
        (field (name "PROVIDED_BY") "SUBCO")
      )
      (libsource (lib "MCD_PARTS_database") (part "SB_ON"))
    )
    (comp (ref "SC1")
      (value "S0951-46R")
      (footprint "CLIP_HARWIN_S0951-46R")
      (description "shield clip Harwin S0951-46R to fix RF shielded cavity")
      (fields
        (field (name "INTERNAL_PART_NUMBER") "MCD-01587")
        (field (name "MANUFACTURER") "HARWIN")
        (field (name "PROVIDED_BY") "SUBCO")
      )
      (libsource (lib "MCD_PARTS_database") (part "Shield-clip_S0951-46R"))
    )
    (comp (ref "SC2")
      (value "S0911-46R")
      (description "shield clip Harwin S0911-46R to fix RF shielded cavity - SMT RFI Shield Clip, Compact (T+R)")
      (fields
        (field (name "INTERNAL_PART_NUMBER") "MCD-02165")
        (field (name "MANUFACTURER") "HARWIN")
        (field (name "PROVIDED_BY") "SUBCO")
      )
      (libsource (lib "MCD_PARTS_database") (part "Shield-clip_S0951-46R"))
    )
    (comp (ref "SC3")
      (value "S0951-46R")
      (footprint "CLIP_HARWIN_S0951-46R")
      (description "shield clip Harwin S0951-46R to fix RF shielded cavity")
      (fields
        (field (name "INTERNAL_PART_NUMBER") "MCD-01587")
        (field (name "MANUFACTURER") "HARWIN")
        (field (name "PROVIDED_BY") "SUBCO")
      )
      (libsource (lib "MCD_PARTS_database") (part "Shield-clip_S0951-46R"))
    )
    (comp (ref "SC4")
      (value "S0951-46R")
      (footprint "CLIP_HARWIN_S0951-46R")
      (description "shield clip Harwin S0951-46R to fix RF shielded cavity")
      (fields
        (field (name "INTERNAL_PART_NUMBER") "MCD-01587")
        (field (name "MANUFACTURER") "HARWIN")
        (field (name "PROVIDED_BY") "SUBCO")
      )
      (libsource (lib "MCD_PARTS_database") (part "Shield-clip_S0951-46R"))
    )
    (comp (ref "SC5")
      (value "S0951-46R")
      (footprint "CLIP_HARWIN_S0951-46R")
      (description "shield clip Harwin S0951-46R to fix RF shielded cavity")
      (fields
        (field (name "INTERNAL_PART_NUMBER") "MCD-01587")
        (field (name "MANUFACTURER") "HARWIN")
        (field (name "PROVIDED_BY") "SUBCO")
      )
      (libsource (lib "MCD_PARTS_database") (part "Shield-clip_S0951-46R"))
    )
    (comp (ref "SC6")
      (value "S0951-46R")
      (footprint "CLIP_HARWIN_S0951-46R")
      (description "shield clip Harwin S0951-46R to fix RF shielded cavity")
      (fields
        (field (name "INTERNAL_PART_NUMBER") "MCD-01587")
        (field (name "MANUFACTURER") "HARWIN")
        (field (name "PROVIDED_BY") "SUBCO")
      )
      (libsource (lib "MCD_PARTS_database") (part "Shield-clip_S0951-46R"))
    )
    (comp (ref "SC7")
      (value "S0951-46R")
      (footprint "CLIP_HARWIN_S0951-46R")
      (description "shield clip Harwin S0951-46R to fix RF shielded cavity")
      (fields
        (field (name "INTERNAL_PART_NUMBER") "MCD-01587")
        (field (name "MANUFACTURER") "HARWIN")
        (field (name "PROVIDED_BY") "SUBCO")
      )
      (libsource (lib "MCD_PARTS_database") (part "Shield-clip_S0951-46R"))
    )
    (comp (ref "SC8")
      (value "S0981-46R")
      (description "shield clip Harwin S0981-46R to fix RF shielded cavity - SMT RFI Shield Clip, Corner (T+R)")
      (fields
        (field (name "INTERNAL_PART_NUMBER") "MCD-02164")
        (field (name "MANUFACTURER") "HARWIN")
        (field (name "PROVIDED_BY") "SUBCO")
      )
      (libsource (lib "MCD_PARTS_database") (part "Shield-clip_S0951-46R"))
    )
    (comp (ref "SC9")
      (value "S0981-46R")
      (description "shield clip Harwin S0981-46R to fix RF shielded cavity - SMT RFI Shield Clip, Corner (T+R)")
      (fields
        (field (name "INTERNAL_PART_NUMBER") "MCD-02164")
        (field (name "MANUFACTURER") "HARWIN")
        (field (name "PROVIDED_BY") "SUBCO")
      )
      (libsource (lib "MCD_PARTS_database") (part "Shield-clip_S0951-46R"))
    )
    (comp (ref "U1")
      (value "BGS13S4N9")
      (footprint "ICC_TSNP-9-3_1P1X1P1_P040")
      (description "Wideband RF SP3T Switch")
      (fields
        (field (name "INTERNAL_PART_NUMBER") "MCD-02018")
        (field (name "MANUFACTURER") "INFINEON")
        (field (name "PROVIDED_BY") "SUBCO")
      )
      (libsource (lib "MCD_PARTS_database") (part "BGS13S4N9"))
    )
    (comp (ref "U3")
      (value "NX3L1T3157GM")
      (footprint "ICC_SOT886_XSON6")
      (description "DC switch - Ultra-Low 0.5ohm  SPDT analog switch")
      (fields
        (field (name "INTERNAL_PART_NUMBER") "MCD-01514")
        (field (name "MANUFACTURER") "NXP")
        (field (name "PROVIDED_BY") "SUBCO")
      )
      (libsource (lib "") (part "NX3L1T3157GM_1"))
    )
    (comp (ref "U4")
      (value "NX3L1T3157GM")
      (footprint "ICC_SOT886_XSON6")
      (description "DC switch - Ultra-Low 0.5ohm  SPDT analog switch")
      (fields
        (field (name "INTERNAL_PART_NUMBER") "MCD-01514")
        (field (name "MANUFACTURER") "NXP")
        (field (name "PROVIDED_BY") "SUBCO")
      )
      (libsource (lib "MCD_PARTS_database") (part "NX3L1T3157GM"))
    )
    (comp (ref "U6")
      (value "STM32WL55JCI7")
      (footprint "ICC_UFBGA73_5X5_P050")
      (description "Multiprotocol Wireless 32-bit MCUwith LPWAN Sub-GHz radio solution")
      (fields
        (field (name "INTERNAL_PART_NUMBER") "MCD-01435")
        (field (name "MANUFACTURER") "STMICROELECTRONICS")
      )
      (libsource (lib "MCD_PARTS_database") (part "STM32WL5x_BGA73"))
    )
    (comp (ref "X3")
      (value "NX2016SA 32MHz")
      (footprint "CRY_NX2016SA_4P")
      (description "Crystal 32MHz, 10pF, +-10 ppm, 50ohm max, SMD")
      (fields
        (field (name "INTERNAL_PART_NUMBER") "MCD-01507")
        (field (name "MANUFACTURER_PART_NUMBER") "NX2016SA 32MHz EXS00A-CS06465")
        (field (name "PROVIDED_BY") "SUBCO")
      )
      (libsource (lib "MCD_PARTS_database") (part "XTAL_4_PINS"))
    )
    (comp (ref "X4")
      (value "32MHz")
      (footprint "CRY_NDK_NT2016SB_4P")
      (description "NT2016SF-32M-END5875A")
      (fields
        (field (name "INTERNAL_PART_NUMBER") "MCD-02240")
        (field (name "MANUFACTURER") "NDK")
        (field (name "MANUFACTURER_PART_NUMBER") "NT2016SF-32M-END5875A")
      )
      (libsource (lib "MCD_PARTS_database") (part "NT2016SB"))
    )
  )
  (nets
    (net (code "1") (name "/FE_CTRL1") (class "Default")
      (node (ref "R27") (pin "1") (pinfunction "1_1") (pintype "passive"))
      (node (ref "U3") (pin "6") (pinfunction "SEL_6") (pintype "passive"))
      (node (ref "U4") (pin "6") (pinfunction "SEL_6") (pintype "passive"))
    )
    (net (code "2") (name "/FE_CTRL2") (class "Default")
      (node (ref "R28") (pin "1") (pinfunction "1_1") (pintype "passive"))
    )
    (net (code "3") (name "/FE_CTRL3") (class "Default")
      (node (ref "SB18") (pin "2") (pinfunction "2_2") (pintype "passive"))
    )
    (net (code "4") (name "/PB0") (class "Default")
      (node (ref "SB20") (pin "1") (pinfunction "1_1") (pintype "passive"))
      (node (ref "U6") (pin "F6") (pinfunction "PB0-VDD_TCXO_F6") (pintype "passive"))
    )
    (net (code "5") (name "/RFI_N") (class "Default")
      (node (ref "C19") (pin "2") (pinfunction "2_2") (pintype "passive"))
      (node (ref "L11") (pin "1") (pinfunction "1_1") (pintype "passive"))
      (node (ref "U6") (pin "H7") (pinfunction "RFI_N_H7") (pintype "passive"))
    )
    (net (code "6") (name "/RFI_P") (class "Default")
      (node (ref "C20") (pin "1") (pinfunction "1_1") (pintype "passive"))
      (node (ref "L11") (pin "2") (pinfunction "2_2") (pintype "passive"))
      (node (ref "U6") (pin "J6") (pinfunction "RFI_P_J6") (pintype "passive"))
    )
    (net (code "7") (name "/XTA") (class "Default")
      (node (ref "C31") (pin "2") (pinfunction "2_2") (pintype "passive"))
      (node (ref "R39") (pin "1") (pinfunction "1_1") (pintype "passive"))
      (node (ref "R41") (pin "2") (pinfunction "2_2") (pintype "passive"))
      (node (ref "U6") (pin "G9") (pinfunction "OSC_IN_G9") (pintype "passive"))
    )
    (net (code "8") (name "GND") (class "Default")
      (node (ref "C11") (pin "1") (pinfunction "1_1") (pintype "passive"))
      (node (ref "C14") (pin "1") (pinfunction "1_1") (pintype "passive"))
      (node (ref "C17") (pin "1") (pinfunction "1_1") (pintype "passive"))
      (node (ref "C19") (pin "1") (pinfunction "1_1") (pintype "passive"))
      (node (ref "C21") (pin "1") (pinfunction "1_1") (pintype "passive"))
      (node (ref "C22") (pin "1") (pinfunction "1_1") (pintype "passive"))
      (node (ref "C24") (pin "2") (pinfunction "2_2") (pintype "passive"))
      (node (ref "C25") (pin "1") (pinfunction "1_1") (pintype "passive"))
      (node (ref "C27") (pin "1") (pinfunction "1_1") (pintype "passive"))
      (node (ref "C30") (pin "1") (pinfunction "1_1") (pintype "passive"))
      (node (ref "C35") (pin "1") (pinfunction "1_1") (pintype "passive"))
      (node (ref "C37") (pin "2") (pinfunction "2_2") (pintype "passive"))
      (node (ref "C38") (pin "1") (pinfunction "1_1") (pintype "passive"))
      (node (ref "C5") (pin "1") (pinfunction "1_1") (pintype "passive"))
      (node (ref "C6") (pin "1") (pinfunction "1_1") (pintype "passive"))
      (node (ref "C7") (pin "1") (pinfunction "1_1") (pintype "passive"))
      (node (ref "C71") (pin "1") (pinfunction "1_1") (pintype "passive"))
      (node (ref "C72") (pin "1") (pinfunction "1_1") (pintype "passive"))
      (node (ref "C73") (pin "1") (pinfunction "1_1") (pintype "passive"))
      (node (ref "C74") (pin "1") (pinfunction "1_1") (pintype "passive"))
      (node (ref "C76") (pin "1") (pinfunction "1_1") (pintype "passive"))
      (node (ref "C77") (pin "2") (pinfunction "2_2") (pintype "passive"))
      (node (ref "C78") (pin "1") (pinfunction "1_1") (pintype "passive"))
      (node (ref "C79") (pin "1") (pinfunction "1_1") (pintype "passive"))
      (node (ref "C8") (pin "1") (pinfunction "1_1") (pintype "passive"))
      (node (ref "C80") (pin "1") (pinfunction "1_1") (pintype "passive"))
      (node (ref "C82") (pin "1") (pinfunction "1_1") (pintype "passive"))
      (node (ref "C85") (pin "1") (pinfunction "1_1") (pintype "passive"))
      (node (ref "C92") (pin "1") (pinfunction "1_1") (pintype "passive"))
      (node (ref "C93") (pin "1") (pinfunction "1_1") (pintype "passive"))
      (node (ref "C97") (pin "1") (pinfunction "1_1") (pintype "passive"))
      (node (ref "CN12") (pin "2") (pinfunction "GND_2") (pintype "passive"))
      (node (ref "CN12") (pin "3") (pinfunction "GND_3") (pintype "passive"))
      (node (ref "CN12") (pin "4") (pinfunction "GND_4") (pintype "passive"))
      (node (ref "CN12") (pin "5") (pinfunction "GND_5") (pintype "passive"))
      (node (ref "CN13") (pin "2") (pinfunction "2_2") (pintype "passive"))
      (node (ref "R41") (pin "1") (pinfunction "1_1") (pintype "passive"))
      (node (ref "SC1") (pin "1") (pinfunction "1_1") (pintype "passive"))
      (node (ref "SC2") (pin "1") (pinfunction "1_1") (pintype "passive"))
      (node (ref "SC3") (pin "1") (pinfunction "1_1") (pintype "passive"))
      (node (ref "SC4") (pin "1") (pinfunction "1_1") (pintype "passive"))
      (node (ref "SC5") (pin "1") (pinfunction "1_1") (pintype "passive"))
      (node (ref "SC6") (pin "1") (pinfunction "1_1") (pintype "passive"))
      (node (ref "SC7") (pin "1") (pinfunction "1_1") (pintype "passive"))
      (node (ref "SC8") (pin "1") (pinfunction "1_1") (pintype "passive"))
      (node (ref "SC9") (pin "1") (pinfunction "1_1") (pintype "passive"))
      (node (ref "U1") (pin "6") (pinfunction "DGND_6") (pintype "passive"))
      (node (ref "U1") (pin "9") (pinfunction "GND_9") (pintype "passive"))
      (node (ref "U3") (pin "2") (pinfunction "GND_2") (pintype "passive"))
      (node (ref "U4") (pin "2") (pinfunction "GND_2") (pintype "passive"))
      (node (ref "U6") (pin "A1") (pinfunction "VSSSMPS_A1") (pintype "passive"))
      (node (ref "U6") (pin "G6") (pinfunction "VSSRF_G6") (pintype "passive"))
      (node (ref "U6") (pin "G7") (pinfunction "VSSRF_G7") (pintype "passive"))
      (node (ref "U6") (pin "G8") (pinfunction "VSSRF_G8") (pintype "passive"))
      (node (ref "U6") (pin "H6") (pinfunction "VSSRF_H6") (pintype "passive"))
      (node (ref "X3") (pin "2") (pinfunction "2_2") (pintype "passive"))
      (node (ref "X3") (pin "4") (pinfunction "4_4") (pintype "passive"))
      (node (ref "X4") (pin "1") (pinfunction "EN_1") (pintype "passive"))
      (node (ref "X4") (pin "2") (pinfunction "GND_2") (pintype "passive"))
    )
    (net (code "9") (name "Net-(C2-Pad1)") (class "Default")
      (node (ref "C2") (pin "1") (pinfunction "1_1") (pintype "passive"))
      (node (ref "C6") (pin "2") (pinfunction "2_2") (pintype "passive"))
      (node (ref "L2") (pin "2") (pinfunction "2_2") (pintype "passive"))
    )
    (net (code "10") (name "Net-(C11-Pad2)") (class "Default")
      (node (ref "C11") (pin "2") (pinfunction "2_2") (pintype "passive"))
      (node (ref "C12") (pin "1") (pinfunction "1_1") (pintype "passive"))
      (node (ref "C15") (pin "2") (pinfunction "2_2") (pintype "passive"))
      (node (ref "L5") (pin "2") (pinfunction "2_2") (pintype "passive"))
    )
    (net (code "11") (name "Net-(C12-Pad2)") (class "Default")
      (node (ref "C12") (pin "2") (pinfunction "2_2") (pintype "passive"))
      (node (ref "L3") (pin "1") (pinfunction "1_1") (pintype "passive"))
    )
    (net (code "12") (name "Net-(C13-Pad1)") (class "Default")
      (node (ref "C13") (pin "1") (pinfunction "1_1") (pintype "passive"))
      (node (ref "L4") (pin "1") (pinfunction "1_1") (pintype "passive"))
    )
    (net (code "13") (name "Net-(C13-Pad2)") (class "Default")
      (node (ref "C13") (pin "2") (pinfunction "2_2") (pintype "passive"))
      (node (ref "C14") (pin "2") (pinfunction "2_2") (pintype "passive"))
      (node (ref "C16") (pin "1") (pinfunction "1_1") (pintype "passive"))
      (node (ref "L6") (pin "2") (pinfunction "2_2") (pintype "passive"))
    )
    (net (code "14") (name "Net-(C15-Pad1)") (class "Default")
      (node (ref "C15") (pin "1") (pinfunction "1_1") (pintype "passive"))
      (node (ref "C22") (pin "2") (pinfunction "2_2") (pintype "passive"))
      (node (ref "L5") (pin "1") (pinfunction "1_1") (pintype "passive"))
      (node (ref "L7") (pin "2") (pinfunction "2_2") (pintype "passive"))
      (node (ref "L9") (pin "2") (pinfunction "2_2") (pintype "passive"))
    )
    (net (code "15") (name "Net-(C16-Pad2)") (class "Default")
      (node (ref "C16") (pin "2") (pinfunction "2_2") (pintype "passive"))
      (node (ref "C21") (pin "2") (pinfunction "2_2") (pintype "passive"))
      (node (ref "L10") (pin "2") (pinfunction "2_2") (pintype "passive"))
      (node (ref "L6") (pin "1") (pinfunction "1_1") (pintype "passive"))
      (node (ref "L8") (pin "2") (pinfunction "2_2") (pintype "passive"))
    )
    (net (code "16") (name "Net-(C30-Pad2)") (class "Default")
      (node (ref "C30") (pin "2") (pinfunction "2_2") (pintype "passive"))
      (node (ref "R39") (pin "2") (pinfunction "2_2") (pintype "passive"))
      (node (ref "X3") (pin "1") (pinfunction "1_1") (pintype "passive"))
    )
    (net (code "17") (name "Net-(C31-Pad1)") (class "Default")
      (node (ref "C31") (pin "1") (pinfunction "1_1") (pintype "passive"))
      (node (ref "R2") (pin "2") (pinfunction "2_2") (pintype "passive"))
    )
    (net (code "18") (name "Net-(C38-Pad2)") (class "Default")
      (node (ref "C38") (pin "2") (pinfunction "2_2") (pintype "passive"))
      (node (ref "R40") (pin "2") (pinfunction "2_2") (pintype "passive"))
      (node (ref "X3") (pin "3") (pinfunction "3_3") (pintype "passive"))
    )
    (net (code "19") (name "Net-(CN12-RF)") (class "Default")
      (node (ref "C5") (pin "2") (pinfunction "2_2") (pintype "passive"))
      (node (ref "CN12") (pin "1") (pinfunction "RF_1") (pintype "passive"))
      (node (ref "L2") (pin "1") (pinfunction "1_1") (pintype "passive"))
    )
    (net (code "20") (name "Net-(CN13-Pad1)") (class "Default")
      (node (ref "CN13") (pin "1") (pinfunction "1_1") (pintype "passive"))
      (node (ref "R33") (pin "1") (pinfunction "1_1") (pintype "passive"))
    )
    (net (code "21") (name "Net-(L13-Pad2)") (class "Default")
      (node (ref "L13") (pin "2") (pinfunction "2_2") (pintype "passive"))
      (node (ref "R32") (pin "2") (pinfunction "2_2") (pintype "passive"))
      (node (ref "R33") (pin "2") (pinfunction "2_2") (pintype "passive"))
    )
    (net (code "22") (name "Net-(R29-Pad2)") (class "Default")
      (node (ref "R29") (pin "2") (pinfunction "2_2") (pintype "passive"))
      (node (ref "SB18") (pin "1") (pinfunction "1_1") (pintype "passive"))
    )
    (net (code "23") (name "Net-(U1-RF1)") (class "Default")
      (node (ref "C17") (pin "2") (pinfunction "2_2") (pintype "passive"))
      (node (ref "C20") (pin "2") (pinfunction "2_2") (pintype "passive"))
      (node (ref "U1") (pin "3") (pinfunction "RF1_3") (pintype "passive"))
    )
    (net (code "24") (name "Net-(U1-RF2)") (class "Default")
      (node (ref "C7") (pin "2") (pinfunction "2_2") (pintype "passive"))
      (node (ref "L3") (pin "2") (pinfunction "2_2") (pintype "passive"))
      (node (ref "U1") (pin "5") (pinfunction "RF2_5") (pintype "passive"))
    )
    (net (code "25") (name "Net-(U1-RF3)") (class "Default")
      (node (ref "C8") (pin "2") (pinfunction "2_2") (pintype "passive"))
      (node (ref "L4") (pin "2") (pinfunction "2_2") (pintype "passive"))
      (node (ref "U1") (pin "2") (pinfunction "RF3_2") (pintype "passive"))
    )
    (net (code "26") (name "Net-(U1-RFin)") (class "Default")
      (node (ref "C2") (pin "2") (pinfunction "2_2") (pintype "passive"))
      (node (ref "U1") (pin "4") (pinfunction "RFin_4") (pintype "passive"))
    )
    (net (code "27") (name "Net-(U1-V1)") (class "Default")
      (node (ref "C72") (pin "2") (pinfunction "2_2") (pintype "passive"))
      (node (ref "R27") (pin "2") (pinfunction "2_2") (pintype "passive"))
      (node (ref "U1") (pin "1") (pinfunction "V1_1") (pintype "passive"))
    )
    (net (code "28") (name "Net-(U1-V2)") (class "Default")
      (node (ref "C71") (pin "2") (pinfunction "2_2") (pintype "passive"))
      (node (ref "R28") (pin "2") (pinfunction "2_2") (pintype "passive"))
      (node (ref "U1") (pin "8") (pinfunction "V2_8") (pintype "passive"))
    )
    (net (code "29") (name "Net-(U1-VDD)") (class "Default")
      (node (ref "C73") (pin "2") (pinfunction "2_2") (pintype "passive"))
      (node (ref "R29") (pin "1") (pinfunction "1_1") (pintype "passive"))
      (node (ref "U1") (pin "7") (pinfunction "VDD_7") (pintype "passive"))
    )
    (net (code "30") (name "Net-(U3-Y0)") (class "Default")
      (node (ref "R37") (pin "1") (pinfunction "1_1") (pintype "passive"))
      (node (ref "U3") (pin "3") (pinfunction "Y0_3") (pintype "passive"))
    )
    (net (code "31") (name "Net-(U3-Y1)") (class "Default")
      (node (ref "R38") (pin "1") (pinfunction "1_1") (pintype "passive"))
      (node (ref "U3") (pin "1") (pinfunction "Y1_1") (pintype "passive"))
    )
    (net (code "32") (name "Net-(U4-Y0)") (class "Default")
      (node (ref "C24") (pin "1") (pinfunction "1_1") (pintype "passive"))
      (node (ref "L7") (pin "1") (pinfunction "1_1") (pintype "passive"))
      (node (ref "U4") (pin "3") (pinfunction "Y0_3") (pintype "passive"))
    )
    (net (code "33") (name "Net-(U4-Y1)") (class "Default")
      (node (ref "C25") (pin "2") (pinfunction "2_2") (pintype "passive"))
      (node (ref "L8") (pin "1") (pinfunction "1_1") (pintype "passive"))
      (node (ref "U4") (pin "1") (pinfunction "Y1_1") (pintype "passive"))
    )
    (net (code "34") (name "Net-(U4-Z)") (class "Default")
      (node (ref "C74") (pin "2") (pinfunction "2_2") (pintype "passive"))
      (node (ref "C76") (pin "2") (pinfunction "2_2") (pintype "passive"))
      (node (ref "C92") (pin "2") (pinfunction "2_2") (pintype "passive"))
      (node (ref "U4") (pin "4") (pinfunction "Z_4") (pintype "passive"))
      (node (ref "U6") (pin "H9") (pinfunction "VR_PA_H9") (pintype "passive"))
    )
    (net (code "35") (name "Net-(U6A-OSC_OUT)") (class "Default")
      (node (ref "R40") (pin "1") (pinfunction "1_1") (pintype "passive"))
      (node (ref "U6") (pin "F8") (pinfunction "OSC_OUT_F8") (pintype "passive"))
    )
    (net (code "36") (name "Net-(U6A-RFO_HP)") (class "Default")
      (node (ref "L9") (pin "1") (pinfunction "1_1") (pintype "passive"))
      (node (ref "U6") (pin "J9") (pinfunction "RFO_HP_J9") (pintype "passive"))
    )
    (net (code "37") (name "Net-(U6A-RFO_LP)") (class "Default")
      (node (ref "L10") (pin "1") (pinfunction "1_1") (pintype "passive"))
      (node (ref "U6") (pin "J8") (pinfunction "RFO_LP_J8") (pintype "passive"))
    )
    (net (code "38") (name "Net-(U6B-VFBSMPS)") (class "Default")
      (node (ref "C85") (pin "2") (pinfunction "2_2") (pintype "passive"))
      (node (ref "L13") (pin "1") (pinfunction "1_1") (pintype "passive"))
      (node (ref "SB22") (pin "2") (pinfunction "2_2") (pintype "passive"))
      (node (ref "U6") (pin "B2") (pinfunction "VFBSMPS_B2") (pintype "passive"))
    )
    (net (code "39") (name "Net-(U6B-VLXSMPS)") (class "Default")
      (node (ref "R32") (pin "1") (pinfunction "1_1") (pintype "passive"))
      (node (ref "U6") (pin "B1") (pinfunction "VLXSMPS_B1") (pintype "passive"))
    )
    (net (code "40") (name "Net-(X4-OUT)") (class "Default")
      (node (ref "R2") (pin "1") (pinfunction "1_1") (pintype "passive"))
      (node (ref "X4") (pin "3") (pinfunction "OUT_3") (pintype "passive"))
    )
    (net (code "41") (name "Net-(X4-VDD)") (class "Default")
      (node (ref "C27") (pin "2") (pinfunction "2_2") (pintype "passive"))
      (node (ref "L12") (pin "1") (pinfunction "1_1") (pintype "passive"))
      (node (ref "X4") (pin "4") (pinfunction "VDD_4") (pintype "passive"))
    )
    (net (code "42") (name "PB0_VDD_TCXO") (class "Default")
      (node (ref "C77") (pin "1") (pinfunction "1_1") (pintype "passive"))
      (node (ref "C79") (pin "2") (pinfunction "2_2") (pintype "passive"))
      (node (ref "C97") (pin "2") (pinfunction "2_2") (pintype "passive"))
      (node (ref "L12") (pin "2") (pinfunction "2_2") (pintype "passive"))
      (node (ref "SB20") (pin "2") (pinfunction "2_2") (pintype "passive"))
    )
    (net (code "43") (name "VDDPA") (class "Default")
      (node (ref "C78") (pin "2") (pinfunction "2_2") (pintype "passive"))
      (node (ref "U3") (pin "4") (pinfunction "Z_4") (pintype "passive"))
      (node (ref "U6") (pin "H8") (pinfunction "VDDPA_H8") (pintype "passive"))
    )
    (net (code "44") (name "VDDRF") (class "Default")
      (node (ref "C82") (pin "2") (pinfunction "2_2") (pintype "passive"))
      (node (ref "C93") (pin "2") (pinfunction "2_2") (pintype "passive"))
      (node (ref "R37") (pin "2") (pinfunction "2_2") (pintype "passive"))
      (node (ref "SB23") (pin "1") (pinfunction "1_1") (pintype "passive"))
      (node (ref "U6") (pin "E8") (pinfunction "VDDRF_E8") (pintype "passive"))
    )
    (net (code "45") (name "VDDRF1V55") (class "Default")
      (node (ref "C80") (pin "2") (pinfunction "2_2") (pintype "passive"))
      (node (ref "R38") (pin "2") (pinfunction "2_2") (pintype "passive"))
      (node (ref "SB22") (pin "1") (pinfunction "1_1") (pintype "passive"))
      (node (ref "U6") (pin "F7") (pinfunction "VDDRF1V55_F7") (pintype "passive"))
    )
    (net (code "46") (name "VDD_APP") (class "Default")
      (node (ref "U3") (pin "5") (pinfunction "VCC_5") (pintype "passive"))
      (node (ref "U4") (pin "5") (pinfunction "VCC_5") (pintype "passive"))
    )
    (net (code "47") (name "VDD_RF") (class "Default")
      (node (ref "C35") (pin "2") (pinfunction "2_2") (pintype "passive"))
      (node (ref "C37") (pin "1") (pinfunction "1_1") (pintype "passive"))
      (node (ref "SB23") (pin "2") (pinfunction "2_2") (pintype "passive"))
      (node (ref "U6") (pin "A2") (pinfunction "VDDSMPS_A2") (pintype "passive"))
    )
  )
)
